# ATX_Power_Distro.net
KiCad netlist of a schematic drawn in EAGLE
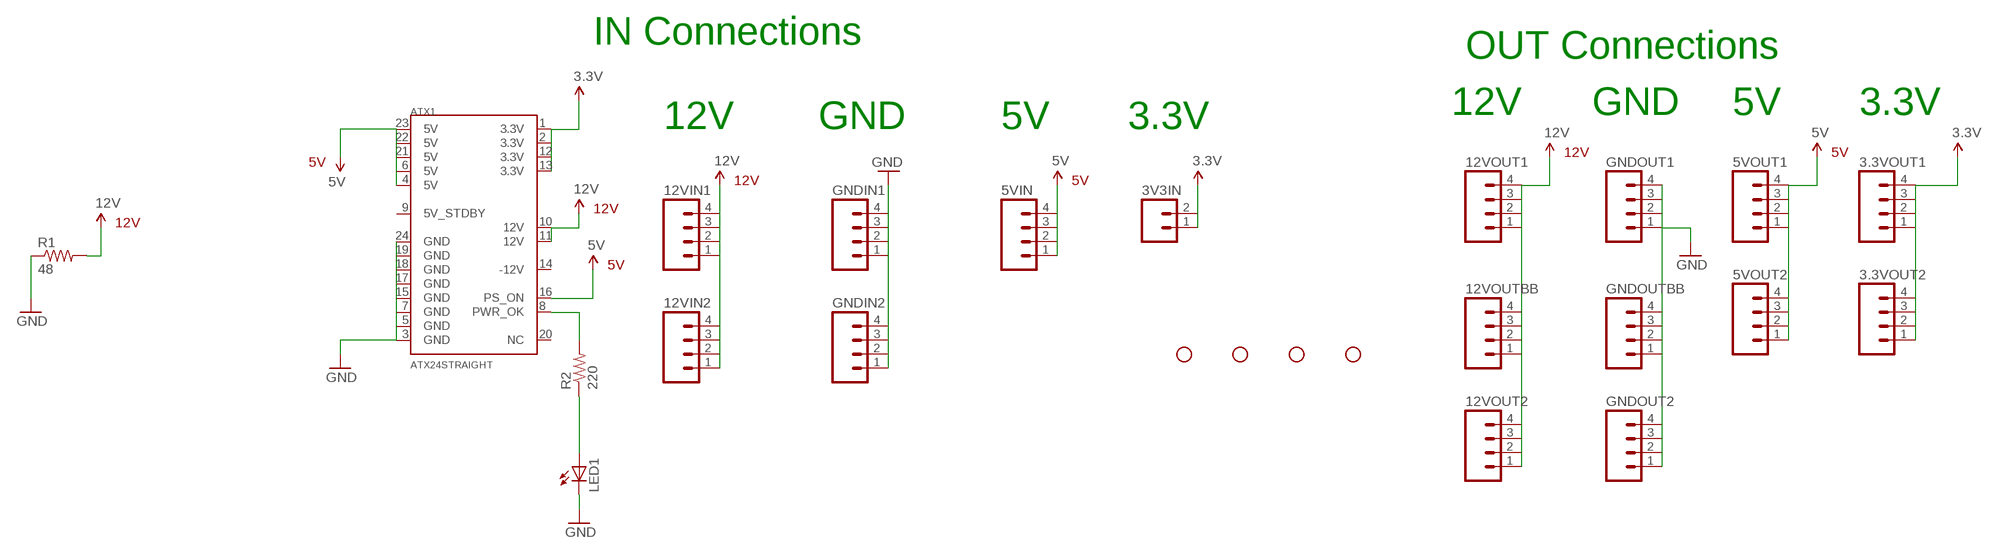
[diagram p0: schematic, sheet 1]

(export (version "E")
  (design (tool "Eeschema 10.0.6"))
  (components
    (comp (ref "3.3VOUT1")
      (value "M04SCREW-5MM")
      (footprint "eagle-import:SCREWTERMINAL-5MM-4")
      (libsource (lib "eagle-import") (part "M04SCREW-5MM"))
    )
    (comp (ref "3.3VOUT2")
      (value "M04SCREW-5MM")
      (footprint "eagle-import:SCREWTERMINAL-5MM-4")
      (libsource (lib "eagle-import") (part "M04SCREW-5MM"))
    )
    (comp (ref "3V3IN")
      (value "M025MM")
      (footprint "eagle-import:SCREWTERMINAL-5MM-2")
      (libsource (lib "eagle-import") (part "M025MM"))
    )
    (comp (ref "5VIN")
      (value "M04SCREW-5MM")
      (footprint "eagle-import:SCREWTERMINAL-5MM-4")
      (libsource (lib "eagle-import") (part "M04SCREW-5MM"))
    )
    (comp (ref "5VOUT1")
      (value "M04SCREW-5MM")
      (footprint "eagle-import:SCREWTERMINAL-5MM-4")
      (libsource (lib "eagle-import") (part "M04SCREW-5MM"))
    )
    (comp (ref "5VOUT2")
      (value "M04SCREW-5MM")
      (footprint "eagle-import:SCREWTERMINAL-5MM-4")
      (libsource (lib "eagle-import") (part "M04SCREW-5MM"))
    )
    (comp (ref "12VIN1")
      (value "M04SCREW-5MM")
      (footprint "eagle-import:SCREWTERMINAL-5MM-4")
      (libsource (lib "eagle-import") (part "M04SCREW-5MM"))
    )
    (comp (ref "12VIN2")
      (value "M04SCREW-5MM")
      (footprint "eagle-import:SCREWTERMINAL-5MM-4")
      (libsource (lib "eagle-import") (part "M04SCREW-5MM"))
    )
    (comp (ref "12VOUT1")
      (value "M04SCREW-5MM")
      (footprint "eagle-import:SCREWTERMINAL-5MM-4")
      (libsource (lib "eagle-import") (part "M04SCREW-5MM"))
    )
    (comp (ref "12VOUT2")
      (value "M04SCREW-5MM")
      (footprint "eagle-import:SCREWTERMINAL-5MM-4")
      (libsource (lib "eagle-import") (part "M04SCREW-5MM"))
    )
    (comp (ref "12VOUTBB")
      (value "M04BARRIER_BLOCK_0.375\"")
      (footprint "eagle-import:1X04_BARRIER_BLOCK_0.375_")
      (libsource (lib "eagle-import") (part "M04BARRIER_BLOCK_0.375{dblquote}"))
    )
    (comp (ref "ATX1")
      (value "ATX24STRAIGHT")
      (footprint "eagle-import:ATX_24")
      (libsource (lib "eagle-import") (part "ATX24STRAIGHT"))
    )
    (comp (ref "GNDIN1")
      (value "M04SCREW-5MM")
      (footprint "eagle-import:SCREWTERMINAL-5MM-4")
      (libsource (lib "eagle-import") (part "M04SCREW-5MM"))
    )
    (comp (ref "GNDIN2")
      (value "M04SCREW-5MM")
      (footprint "eagle-import:SCREWTERMINAL-5MM-4")
      (libsource (lib "eagle-import") (part "M04SCREW-5MM"))
    )
    (comp (ref "GNDOUT1")
      (value "M04SCREW-5MM")
      (footprint "eagle-import:SCREWTERMINAL-5MM-4")
      (libsource (lib "eagle-import") (part "M04SCREW-5MM"))
    )
    (comp (ref "GNDOUT2")
      (value "M04SCREW-5MM")
      (footprint "eagle-import:SCREWTERMINAL-5MM-4")
      (libsource (lib "eagle-import") (part "M04SCREW-5MM"))
    )
    (comp (ref "GNDOUTBB")
      (value "M04BARRIER_BLOCK_0.375\"")
      (footprint "eagle-import:1X04_BARRIER_BLOCK_0.375_")
      (libsource (lib "eagle-import") (part "M04BARRIER_BLOCK_0.375{dblquote}"))
    )
    (comp (ref "JP1")
      (value "STAND-OFF")
      (footprint "eagle-import:STAND-OFF")
      (libsource (lib "eagle-import") (part "STAND-OFF"))
    )
    (comp (ref "JP2")
      (value "STAND-OFF")
      (footprint "eagle-import:STAND-OFF")
      (libsource (lib "eagle-import") (part "STAND-OFF"))
    )
    (comp (ref "JP3")
      (value "STAND-OFF")
      (footprint "eagle-import:STAND-OFF")
      (libsource (lib "eagle-import") (part "STAND-OFF"))
    )
    (comp (ref "JP4")
      (value "STAND-OFF")
      (footprint "eagle-import:STAND-OFF")
      (libsource (lib "eagle-import") (part "STAND-OFF"))
    )
    (comp (ref "LED1")
      (value "LED1206")
      (footprint "eagle-import:LED-1206")
      (libsource (lib "eagle-import") (part "LED1206"))
    )
    (comp (ref "R1")
      (value "48")
      (footprint "eagle-import:TO220-2PIN")
      (libsource (lib "eagle-import") (part "RESISTORTO-220-15W"))
    )
    (comp (ref "R2")
      (value "220")
      (footprint "eagle-import:1206")
      (libsource (lib "eagle-import") (part "RESISTOR1206"))
    )
  )
  (nets
    (net (code "1") (name "3.3V") (class "Default")
      (node (ref "3.3VOUT1") (pin "1") (pinfunction "1_1") (pintype "passive"))
      (node (ref "3.3VOUT1") (pin "2") (pinfunction "2_2") (pintype "passive"))
      (node (ref "3.3VOUT1") (pin "3") (pinfunction "3_3") (pintype "passive"))
      (node (ref "3.3VOUT1") (pin "4") (pinfunction "4_4") (pintype "passive"))
      (node (ref "3.3VOUT2") (pin "1") (pinfunction "1_1") (pintype "passive"))
      (node (ref "3.3VOUT2") (pin "2") (pinfunction "2_2") (pintype "passive"))
      (node (ref "3.3VOUT2") (pin "3") (pinfunction "3_3") (pintype "passive"))
      (node (ref "3.3VOUT2") (pin "4") (pinfunction "4_4") (pintype "passive"))
      (node (ref "3V3IN") (pin "1") (pinfunction "1_1") (pintype "passive"))
      (node (ref "3V3IN") (pin "2") (pinfunction "2_2") (pintype "passive"))
      (node (ref "ATX1") (pin "1") (pinfunction "3.3V_1") (pintype "bidirectional"))
      (node (ref "ATX1") (pin "12") (pinfunction "3.3V_12") (pintype "bidirectional"))
      (node (ref "ATX1") (pin "13") (pinfunction "3.3V_13") (pintype "bidirectional"))
      (node (ref "ATX1") (pin "2") (pinfunction "3.3V_2") (pintype "bidirectional"))
    )
    (net (code "2") (name "5V") (class "Default")
      (node (ref "5VIN") (pin "1") (pinfunction "1_1") (pintype "passive"))
      (node (ref "5VIN") (pin "2") (pinfunction "2_2") (pintype "passive"))
      (node (ref "5VIN") (pin "3") (pinfunction "3_3") (pintype "passive"))
      (node (ref "5VIN") (pin "4") (pinfunction "4_4") (pintype "passive"))
      (node (ref "5VOUT1") (pin "1") (pinfunction "1_1") (pintype "passive"))
      (node (ref "5VOUT1") (pin "2") (pinfunction "2_2") (pintype "passive"))
      (node (ref "5VOUT1") (pin "3") (pinfunction "3_3") (pintype "passive"))
      (node (ref "5VOUT1") (pin "4") (pinfunction "4_4") (pintype "passive"))
      (node (ref "5VOUT2") (pin "1") (pinfunction "1_1") (pintype "passive"))
      (node (ref "5VOUT2") (pin "2") (pinfunction "2_2") (pintype "passive"))
      (node (ref "5VOUT2") (pin "3") (pinfunction "3_3") (pintype "passive"))
      (node (ref "5VOUT2") (pin "4") (pinfunction "4_4") (pintype "passive"))
      (node (ref "ATX1") (pin "16") (pinfunction "PS_ON_16") (pintype "bidirectional"))
      (node (ref "ATX1") (pin "21") (pinfunction "5V_21") (pintype "bidirectional"))
      (node (ref "ATX1") (pin "22") (pinfunction "5V_22") (pintype "bidirectional"))
      (node (ref "ATX1") (pin "23") (pinfunction "5V_23") (pintype "bidirectional"))
      (node (ref "ATX1") (pin "4") (pinfunction "5V_4") (pintype "bidirectional"))
      (node (ref "ATX1") (pin "6") (pinfunction "5V_6") (pintype "bidirectional"))
    )
    (net (code "3") (name "12V") (class "Default")
      (node (ref "12VIN1") (pin "1") (pinfunction "1_1") (pintype "passive"))
      (node (ref "12VIN1") (pin "2") (pinfunction "2_2") (pintype "passive"))
      (node (ref "12VIN1") (pin "3") (pinfunction "3_3") (pintype "passive"))
      (node (ref "12VIN1") (pin "4") (pinfunction "4_4") (pintype "passive"))
      (node (ref "12VIN2") (pin "1") (pinfunction "1_1") (pintype "passive"))
      (node (ref "12VIN2") (pin "2") (pinfunction "2_2") (pintype "passive"))
      (node (ref "12VIN2") (pin "3") (pinfunction "3_3") (pintype "passive"))
      (node (ref "12VIN2") (pin "4") (pinfunction "4_4") (pintype "passive"))
      (node (ref "12VOUT1") (pin "1") (pinfunction "1_1") (pintype "passive"))
      (node (ref "12VOUT1") (pin "2") (pinfunction "2_2") (pintype "passive"))
      (node (ref "12VOUT1") (pin "3") (pinfunction "3_3") (pintype "passive"))
      (node (ref "12VOUT1") (pin "4") (pinfunction "4_4") (pintype "passive"))
      (node (ref "12VOUT2") (pin "1") (pinfunction "1_1") (pintype "passive"))
      (node (ref "12VOUT2") (pin "2") (pinfunction "2_2") (pintype "passive"))
      (node (ref "12VOUT2") (pin "3") (pinfunction "3_3") (pintype "passive"))
      (node (ref "12VOUT2") (pin "4") (pinfunction "4_4") (pintype "passive"))
      (node (ref "12VOUTBB") (pin "1") (pinfunction "1_1") (pintype "passive"))
      (node (ref "12VOUTBB") (pin "2") (pinfunction "2_2") (pintype "passive"))
      (node (ref "12VOUTBB") (pin "3") (pinfunction "3_3") (pintype "passive"))
      (node (ref "12VOUTBB") (pin "4") (pinfunction "4_4") (pintype "passive"))
      (node (ref "ATX1") (pin "10") (pinfunction "12V_10") (pintype "bidirectional"))
      (node (ref "ATX1") (pin "11") (pinfunction "12V_11") (pintype "bidirectional"))
      (node (ref "R1") (pin "2") (pinfunction "2_2") (pintype "passive"))
    )
    (net (code "4") (name "GND") (class "Default")
      (node (ref "ATX1") (pin "15") (pinfunction "GND_15") (pintype "bidirectional"))
      (node (ref "ATX1") (pin "17") (pinfunction "GND_17") (pintype "bidirectional"))
      (node (ref "ATX1") (pin "18") (pinfunction "GND_18") (pintype "bidirectional"))
      (node (ref "ATX1") (pin "19") (pinfunction "GND_19") (pintype "bidirectional"))
      (node (ref "ATX1") (pin "24") (pinfunction "GND_24") (pintype "bidirectional"))
      (node (ref "ATX1") (pin "3") (pinfunction "GND_3") (pintype "bidirectional"))
      (node (ref "ATX1") (pin "5") (pinfunction "GND_5") (pintype "bidirectional"))
      (node (ref "ATX1") (pin "7") (pinfunction "GND_7") (pintype "bidirectional"))
      (node (ref "GNDIN1") (pin "1") (pinfunction "1_1") (pintype "passive"))
      (node (ref "GNDIN1") (pin "2") (pinfunction "2_2") (pintype "passive"))
      (node (ref "GNDIN1") (pin "3") (pinfunction "3_3") (pintype "passive"))
      (node (ref "GNDIN1") (pin "4") (pinfunction "4_4") (pintype "passive"))
      (node (ref "GNDIN2") (pin "1") (pinfunction "1_1") (pintype "passive"))
      (node (ref "GNDIN2") (pin "2") (pinfunction "2_2") (pintype "passive"))
      (node (ref "GNDIN2") (pin "3") (pinfunction "3_3") (pintype "passive"))
      (node (ref "GNDIN2") (pin "4") (pinfunction "4_4") (pintype "passive"))
      (node (ref "GNDOUT1") (pin "1") (pinfunction "1_1") (pintype "passive"))
      (node (ref "GNDOUT1") (pin "2") (pinfunction "2_2") (pintype "passive"))
      (node (ref "GNDOUT1") (pin "3") (pinfunction "3_3") (pintype "passive"))
      (node (ref "GNDOUT1") (pin "4") (pinfunction "4_4") (pintype "passive"))
      (node (ref "GNDOUT2") (pin "1") (pinfunction "1_1") (pintype "passive"))
      (node (ref "GNDOUT2") (pin "2") (pinfunction "2_2") (pintype "passive"))
      (node (ref "GNDOUT2") (pin "3") (pinfunction "3_3") (pintype "passive"))
      (node (ref "GNDOUT2") (pin "4") (pinfunction "4_4") (pintype "passive"))
      (node (ref "GNDOUTBB") (pin "1") (pinfunction "1_1") (pintype "passive"))
      (node (ref "GNDOUTBB") (pin "2") (pinfunction "2_2") (pintype "passive"))
      (node (ref "GNDOUTBB") (pin "3") (pinfunction "3_3") (pintype "passive"))
      (node (ref "GNDOUTBB") (pin "4") (pinfunction "4_4") (pintype "passive"))
      (node (ref "LED1") (pin "C") (pinfunction "C_C") (pintype "passive"))
      (node (ref "R1") (pin "1") (pinfunction "1_1") (pintype "passive"))
    )
    (net (code "5") (name "Net-(ATX1-PWR_OK)") (class "Default")
      (node (ref "ATX1") (pin "8") (pinfunction "PWR_OK_8") (pintype "bidirectional"))
      (node (ref "R2") (pin "2") (pinfunction "2_2") (pintype "passive"))
    )
    (net (code "6") (name "Net-(LED1-PadA)") (class "Default")
      (node (ref "LED1") (pin "A") (pinfunction "A_A") (pintype "passive"))
      (node (ref "R2") (pin "1") (pinfunction "1_1") (pintype "passive"))
    )
    (net (code "7") (name "unconnected-(ATX1--12V-Pad14)") (class "Default")
      (node (ref "ATX1") (pin "14") (pinfunction "-12V_14") (pintype "bidirectional"))
    )
    (net (code "8") (name "unconnected-(ATX1-5V_STDBY-Pad9)") (class "Default")
      (node (ref "ATX1") (pin "9") (pinfunction "5V_STDBY_9") (pintype "bidirectional"))
    )
    (net (code "9") (name "unconnected-(ATX1-NC-Pad20)") (class "Default")
      (node (ref "ATX1") (pin "20") (pinfunction "NC_20") (pintype "bidirectional"))
    )
  )
)
